# mainboard_v2.net
KiCad netlist of a schematic drawn in EAGLE
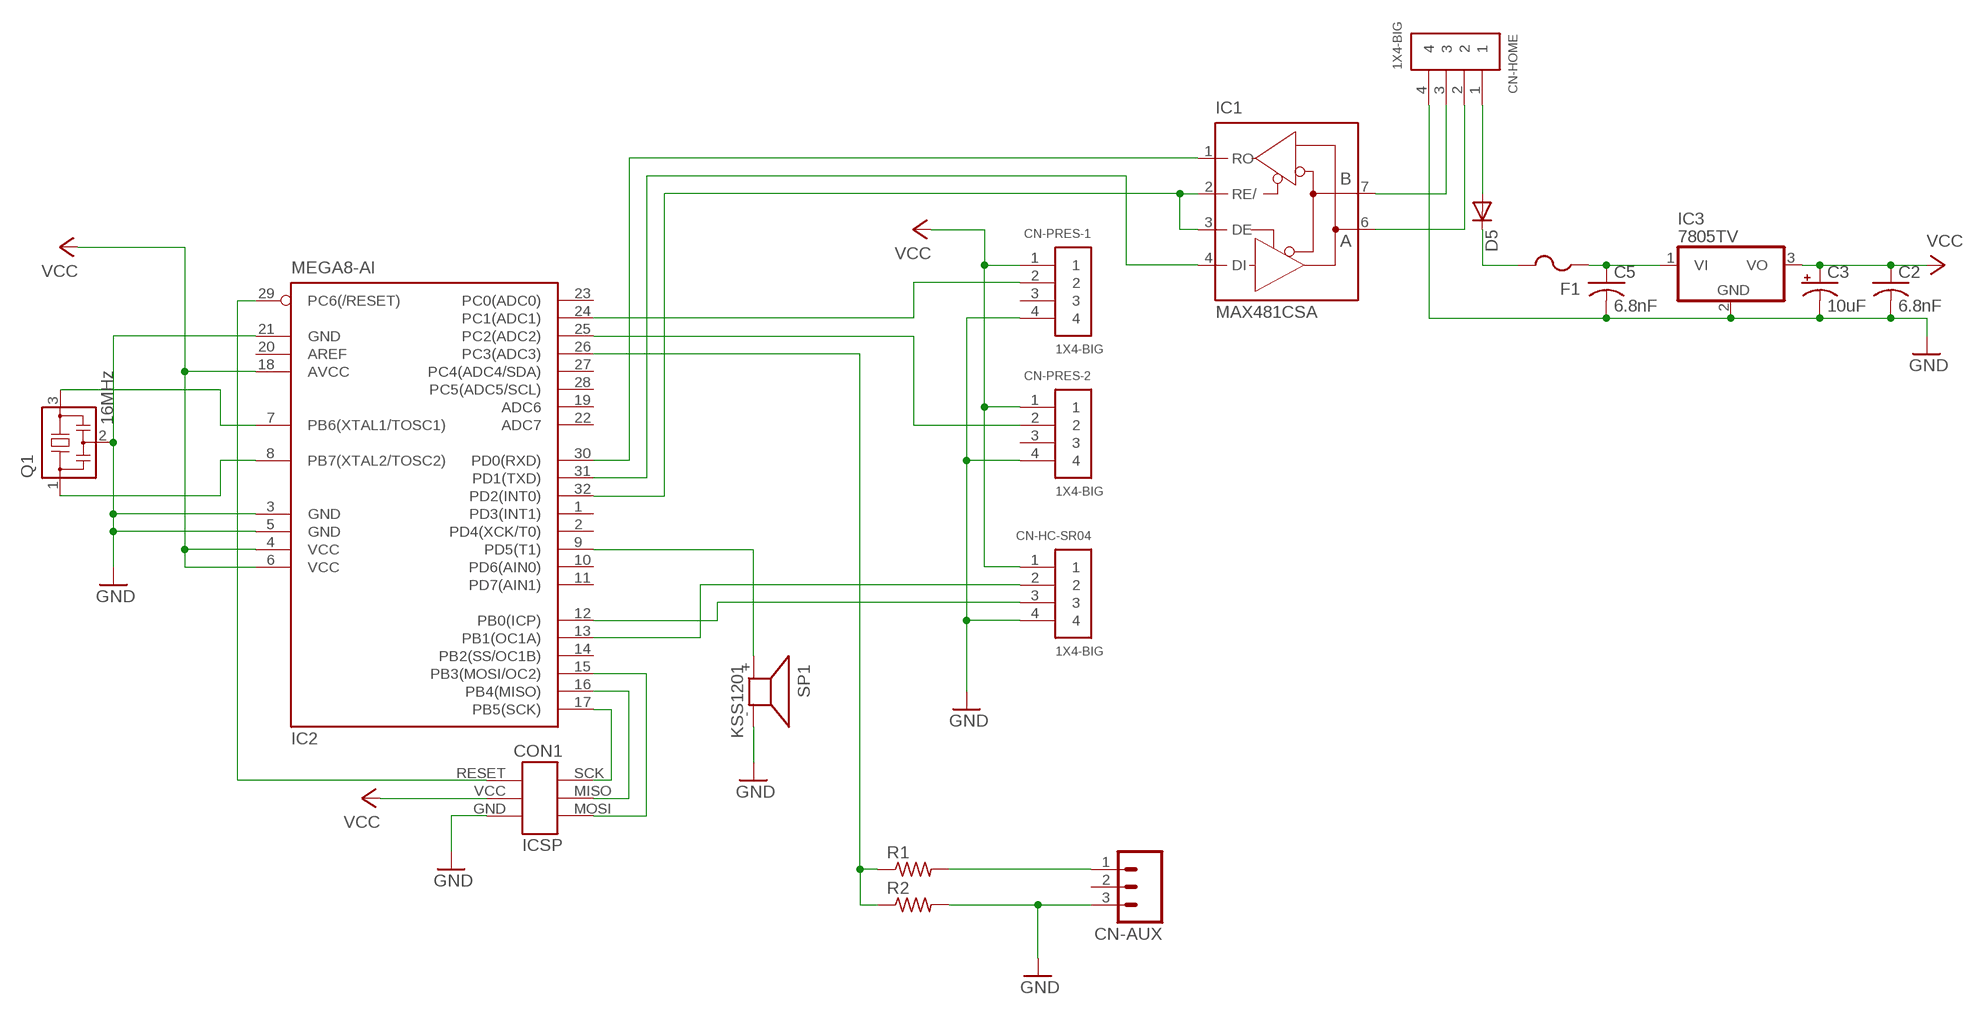
[diagram p0: schematic, sheet 1]

(export (version "E")
  (design (tool "Eeschema 10.0.6"))
  (components
    (comp (ref "C2")
      (value "6.8nF")
      (footprint "eagle-import:C050-024X044")
      (libsource (lib "eagle-import") (part "C-US050-024X044"))
    )
    (comp (ref "C3")
      (value "10uF")
      (footprint "eagle-import:E1,8-4")
      (libsource (lib "eagle-import") (part "CPOL-USE1.8-4"))
    )
    (comp (ref "C5")
      (value "6.8nF")
      (footprint "eagle-import:C050-024X044")
      (libsource (lib "eagle-import") (part "C-US050-024X044"))
    )
    (comp (ref "CN-AUX")
      (value "M03")
      (footprint "eagle-import:03P")
      (libsource (lib "eagle-import") (part "M03"))
    )
    (comp (ref "CN-HC-SR04")
      (value "1X4-BIG")
      (footprint "eagle-import:1X04-BIG")
      (libsource (lib "eagle-import") (part "1X4-BIG"))
    )
    (comp (ref "CN-HOME")
      (value "1X4-BIG")
      (footprint "eagle-import:1X04-BIG")
      (libsource (lib "eagle-import") (part "1X4-BIG"))
    )
    (comp (ref "CN-PRES-1")
      (value "1X4-BIG")
      (footprint "eagle-import:1X04-BIG")
      (libsource (lib "eagle-import") (part "1X4-BIG"))
    )
    (comp (ref "CN-PRES-2")
      (value "1X4-BIG")
      (footprint "eagle-import:1X04-BIG")
      (libsource (lib "eagle-import") (part "1X4-BIG"))
    )
    (comp (ref "CON1")
      (value "ICSP-HEADER")
      (footprint "eagle-import:ICSP-HEADER")
      (libsource (lib "eagle-import") (part "ICSP-HEADER"))
    )
    (comp (ref "D5")
      (value "DIODE-MICROMELF-W")
      (footprint "eagle-import:MICROMELF-W")
      (libsource (lib "eagle-import") (part "DIODE-MICROMELF-W"))
    )
    (comp (ref "F1")
      (value "PTCFUSE-1206")
      (footprint "eagle-import:R1206")
      (libsource (lib "eagle-import") (part "PTCFUSE-1206"))
    )
    (comp (ref "IC1")
      (value "MAX481CSA")
      (footprint "eagle-import:SO08")
      (fields (field (name "MF") "MAXIM"))
      (libsource (lib "eagle-import") (part "MAX481CSA"))
    )
    (comp (ref "IC2")
      (value "MEGA8-AI")
      (footprint "eagle-import:TQFP32-08")
      (fields (field (name "MPN") "ATMEGA8-16AU"))
      (libsource (lib "eagle-import") (part "MEGA8-AI"))
    )
    (comp (ref "IC3")
      (value "7805TV")
      (footprint "eagle-import:TO220V")
      (libsource (lib "eagle-import") (part "78TV05"))
    )
    (comp (ref "Q1")
      (value "16MHz")
      (footprint "eagle-import:RESONATOR")
      (libsource (lib "eagle-import") (part "RESONATOR"))
    )
    (comp (ref "R1")
      (value "R-US_R0603")
      (footprint "eagle-import:R0603")
      (libsource (lib "eagle-import") (part "R-US_R0603"))
    )
    (comp (ref "R2")
      (value "R-US_R0603")
      (footprint "eagle-import:R0603")
      (libsource (lib "eagle-import") (part "R-US_R0603"))
    )
    (comp (ref "SP1")
      (value "KSS1201")
      (footprint "eagle-import:KSS1201")
      (libsource (lib "eagle-import") (part "KSS1201"))
    )
  )
  (nets
    (net (code "1") (name "GND") (class "Default")
      (node (ref "C2") (pin "2") (pinfunction "2_2") (pintype "passive"))
      (node (ref "C3") (pin "-") (pinfunction "-_-") (pintype "passive"))
      (node (ref "C5") (pin "2") (pinfunction "2_2") (pintype "passive"))
      (node (ref "CN-AUX") (pin "3") (pinfunction "3_3") (pintype "passive"))
      (node (ref "CN-HC-SR04") (pin "4") (pinfunction "4_4") (pintype "bidirectional"))
      (node (ref "CN-HOME") (pin "4") (pinfunction "4_4") (pintype "bidirectional"))
      (node (ref "CN-PRES-1") (pin "4") (pinfunction "4_4") (pintype "bidirectional"))
      (node (ref "CN-PRES-2") (pin "4") (pinfunction "4_4") (pintype "bidirectional"))
      (node (ref "CON1") (pin "GND") (pinfunction "GND_GND") (pintype "bidirectional"))
      (node (ref "IC2") (pin "21") (pinfunction "GND_21") (pintype "power_in"))
      (node (ref "IC2") (pin "3") (pinfunction "GND_3") (pintype "power_in"))
      (node (ref "IC2") (pin "5") (pinfunction "GND_5") (pintype "power_in"))
      (node (ref "IC3") (pin "2") (pinfunction "GND_2") (pintype "passive"))
      (node (ref "Q1") (pin "2") (pinfunction "2_2") (pintype "passive"))
      (node (ref "R2") (pin "2") (pinfunction "2_2") (pintype "passive"))
      (node (ref "SP1") (pin "-") (pinfunction "2_-") (pintype "passive"))
    )
    (net (code "2") (name "Net-(CN-AUX-Pad1)") (class "Default")
      (node (ref "CN-AUX") (pin "1") (pinfunction "1_1") (pintype "passive"))
      (node (ref "R1") (pin "2") (pinfunction "2_2") (pintype "passive"))
    )
    (net (code "3") (name "Net-(CN-HOME-Pad1)") (class "Default")
      (node (ref "CN-HOME") (pin "1") (pinfunction "1_1") (pintype "bidirectional"))
      (node (ref "D5") (pin "A") (pinfunction "A_A") (pintype "passive"))
    )
    (net (code "4") (name "Net-(D5-PadC)") (class "Default")
      (node (ref "D5") (pin "C") (pinfunction "C_C") (pintype "passive"))
      (node (ref "F1") (pin "2") (pinfunction "2_2") (pintype "passive"))
    )
    (net (code "5") (name "Net-(IC1A-A)") (class "Default")
      (node (ref "CN-HOME") (pin "2") (pinfunction "2_2") (pintype "bidirectional"))
      (node (ref "IC1") (pin "6") (pinfunction "A_6") (pintype "passive"))
    )
    (net (code "6") (name "Net-(IC1A-B)") (class "Default")
      (node (ref "CN-HOME") (pin "3") (pinfunction "3_3") (pintype "bidirectional"))
      (node (ref "IC1") (pin "7") (pinfunction "B_7") (pintype "passive"))
    )
    (net (code "7") (name "Net-(IC1A-DE)") (class "Default")
      (node (ref "IC1") (pin "2") (pinfunction "RE/_2") (pintype "input"))
      (node (ref "IC1") (pin "3") (pinfunction "DE_3") (pintype "input"))
      (node (ref "IC2") (pin "32") (pinfunction "PD2(INT0)_32") (pintype "bidirectional"))
    )
    (net (code "8") (name "Net-(IC1A-DI)") (class "Default")
      (node (ref "IC1") (pin "4") (pinfunction "DI_4") (pintype "input"))
      (node (ref "IC2") (pin "31") (pinfunction "PD1(TXD)_31") (pintype "bidirectional"))
    )
    (net (code "9") (name "Net-(IC1A-RO)") (class "Default")
      (node (ref "IC1") (pin "1") (pinfunction "RO_1") (pintype "output"))
      (node (ref "IC2") (pin "30") (pinfunction "PD0(RXD)_30") (pintype "bidirectional"))
    )
    (net (code "10") (name "Net-(IC2-PB0(ICP))") (class "Default")
      (node (ref "CN-HC-SR04") (pin "3") (pinfunction "3_3") (pintype "bidirectional"))
      (node (ref "IC2") (pin "12") (pinfunction "PB0(ICP)_12") (pintype "bidirectional"))
    )
    (net (code "11") (name "Net-(IC2-PB1(OC1A))") (class "Default")
      (node (ref "CN-HC-SR04") (pin "2") (pinfunction "2_2") (pintype "bidirectional"))
      (node (ref "IC2") (pin "13") (pinfunction "PB1(OC1A)_13") (pintype "bidirectional"))
    )
    (net (code "12") (name "Net-(IC2-PB3(MOSI{slash}OC2))") (class "Default")
      (node (ref "CON1") (pin "MOSI") (pinfunction "MOSI_MOSI") (pintype "bidirectional"))
      (node (ref "IC2") (pin "15") (pinfunction "PB3(MOSI/OC2)_15") (pintype "bidirectional"))
    )
    (net (code "13") (name "Net-(IC2-PB4(MISO))") (class "Default")
      (node (ref "CON1") (pin "MISO") (pinfunction "MISO_MISO") (pintype "bidirectional"))
      (node (ref "IC2") (pin "16") (pinfunction "PB4(MISO)_16") (pintype "bidirectional"))
    )
    (net (code "14") (name "Net-(IC2-PB5(SCK))") (class "Default")
      (node (ref "CON1") (pin "SCK") (pinfunction "SCK_SCK") (pintype "bidirectional"))
      (node (ref "IC2") (pin "17") (pinfunction "PB5(SCK)_17") (pintype "bidirectional"))
    )
    (net (code "15") (name "Net-(IC2-PB6(XTAL1{slash}TOSC1))") (class "Default")
      (node (ref "IC2") (pin "7") (pinfunction "PB6(XTAL1/TOSC1)_7") (pintype "bidirectional"))
      (node (ref "Q1") (pin "3") (pinfunction "3_3") (pintype "passive"))
    )
    (net (code "16") (name "Net-(IC2-PB7(XTAL2{slash}TOSC2))") (class "Default")
      (node (ref "IC2") (pin "8") (pinfunction "PB7(XTAL2/TOSC2)_8") (pintype "bidirectional"))
      (node (ref "Q1") (pin "1") (pinfunction "1_1") (pintype "passive"))
    )
    (net (code "17") (name "Net-(IC2-PC1(ADC1))") (class "Default")
      (node (ref "CN-PRES-1") (pin "2") (pinfunction "2_2") (pintype "bidirectional"))
      (node (ref "IC2") (pin "24") (pinfunction "PC1(ADC1)_24") (pintype "bidirectional"))
    )
    (net (code "18") (name "Net-(IC2-PC2(ADC2))") (class "Default")
      (node (ref "CN-PRES-2") (pin "2") (pinfunction "2_2") (pintype "bidirectional"))
      (node (ref "IC2") (pin "25") (pinfunction "PC2(ADC2)_25") (pintype "bidirectional"))
    )
    (net (code "19") (name "Net-(IC2-PC3(ADC3))") (class "Default")
      (node (ref "IC2") (pin "26") (pinfunction "PC3(ADC3)_26") (pintype "bidirectional"))
      (node (ref "R1") (pin "1") (pinfunction "1_1") (pintype "passive"))
      (node (ref "R2") (pin "1") (pinfunction "1_1") (pintype "passive"))
    )
    (net (code "20") (name "Net-(IC2-PC6({slash}RESET))") (class "Default")
      (node (ref "CON1") (pin "RESET") (pinfunction "RESET_RESET") (pintype "bidirectional"))
      (node (ref "IC2") (pin "29") (pinfunction "PC6(/RESET)_29") (pintype "bidirectional"))
    )
    (net (code "21") (name "Net-(IC2-PD5(T1))") (class "Default")
      (node (ref "IC2") (pin "9") (pinfunction "PD5(T1)_9") (pintype "bidirectional"))
      (node (ref "SP1") (pin "+") (pinfunction "1_+") (pintype "passive"))
    )
    (net (code "22") (name "Net-(IC3-VI)") (class "Default")
      (node (ref "C5") (pin "1") (pinfunction "1_1") (pintype "passive"))
      (node (ref "F1") (pin "1") (pinfunction "1_1") (pintype "passive"))
      (node (ref "IC3") (pin "1") (pinfunction "VI_1") (pintype "input"))
    )
    (net (code "23") (name "VCC") (class "Default")
      (node (ref "C2") (pin "1") (pinfunction "1_1") (pintype "passive"))
      (node (ref "C3") (pin "+") (pinfunction "+_+") (pintype "passive"))
      (node (ref "CN-HC-SR04") (pin "1") (pinfunction "1_1") (pintype "bidirectional"))
      (node (ref "CN-PRES-1") (pin "1") (pinfunction "1_1") (pintype "bidirectional"))
      (node (ref "CN-PRES-2") (pin "1") (pinfunction "1_1") (pintype "bidirectional"))
      (node (ref "CON1") (pin "VCC") (pinfunction "+5V_VCC") (pintype "bidirectional"))
      (node (ref "IC2") (pin "18") (pinfunction "AVCC_18") (pintype "power_in"))
      (node (ref "IC2") (pin "4") (pinfunction "VCC_4") (pintype "power_in"))
      (node (ref "IC2") (pin "6") (pinfunction "VCC_6") (pintype "power_in"))
      (node (ref "IC3") (pin "3") (pinfunction "VO_3") (pintype "passive"))
    )
    (net (code "24") (name "unconnected-(CN-AUX-Pad2)") (class "Default")
      (node (ref "CN-AUX") (pin "2") (pinfunction "2_2") (pintype "passive"))
    )
    (net (code "25") (name "unconnected-(CN-PRES-1-Pad3)") (class "Default")
      (node (ref "CN-PRES-1") (pin "3") (pinfunction "3_3") (pintype "bidirectional"))
    )
    (net (code "26") (name "unconnected-(CN-PRES-2-Pad3)") (class "Default")
      (node (ref "CN-PRES-2") (pin "3") (pinfunction "3_3") (pintype "bidirectional"))
    )
    (net (code "27") (name "unconnected-(IC2-ADC6-Pad19)") (class "Default")
      (node (ref "IC2") (pin "19") (pinfunction "ADC6_19") (pintype "bidirectional"))
    )
    (net (code "28") (name "unconnected-(IC2-ADC7-Pad22)") (class "Default")
      (node (ref "IC2") (pin "22") (pinfunction "ADC7_22") (pintype "bidirectional"))
    )
    (net (code "29") (name "unconnected-(IC2-AREF-Pad20)") (class "Default")
      (node (ref "IC2") (pin "20") (pinfunction "AREF_20") (pintype "passive"))
    )
    (net (code "30") (name "unconnected-(IC2-PB2(SS{slash}OC1B)-Pad14)") (class "Default")
      (node (ref "IC2") (pin "14") (pinfunction "PB2(SS/OC1B)_14") (pintype "bidirectional"))
    )
    (net (code "31") (name "unconnected-(IC2-PC0(ADC0)-Pad23)") (class "Default")
      (node (ref "IC2") (pin "23") (pinfunction "PC0(ADC0)_23") (pintype "bidirectional"))
    )
    (net (code "32") (name "unconnected-(IC2-PC4(ADC4{slash}SDA)-Pad27)") (class "Default")
      (node (ref "IC2") (pin "27") (pinfunction "PC4(ADC4/SDA)_27") (pintype "bidirectional"))
    )
    (net (code "33") (name "unconnected-(IC2-PC5(ADC5{slash}SCL)-Pad28)") (class "Default")
      (node (ref "IC2") (pin "28") (pinfunction "PC5(ADC5/SCL)_28") (pintype "bidirectional"))
    )
    (net (code "34") (name "unconnected-(IC2-PD3(INT1)-Pad1)") (class "Default")
      (node (ref "IC2") (pin "1") (pinfunction "PD3(INT1)_1") (pintype "bidirectional"))
    )
    (net (code "35") (name "unconnected-(IC2-PD4(XCK{slash}T0)-Pad2)") (class "Default")
      (node (ref "IC2") (pin "2") (pinfunction "PD4(XCK/T0)_2") (pintype "bidirectional"))
    )
    (net (code "36") (name "unconnected-(IC2-PD6(AIN0)-Pad10)") (class "Default")
      (node (ref "IC2") (pin "10") (pinfunction "PD6(AIN0)_10") (pintype "bidirectional"))
    )
    (net (code "37") (name "unconnected-(IC2-PD7(AIN1)-Pad11)") (class "Default")
      (node (ref "IC2") (pin "11") (pinfunction "PD7(AIN1)_11") (pintype "bidirectional"))
    )
  )
)
